# FoneAstra.net
KiCad netlist of a schematic drawn in EAGLE
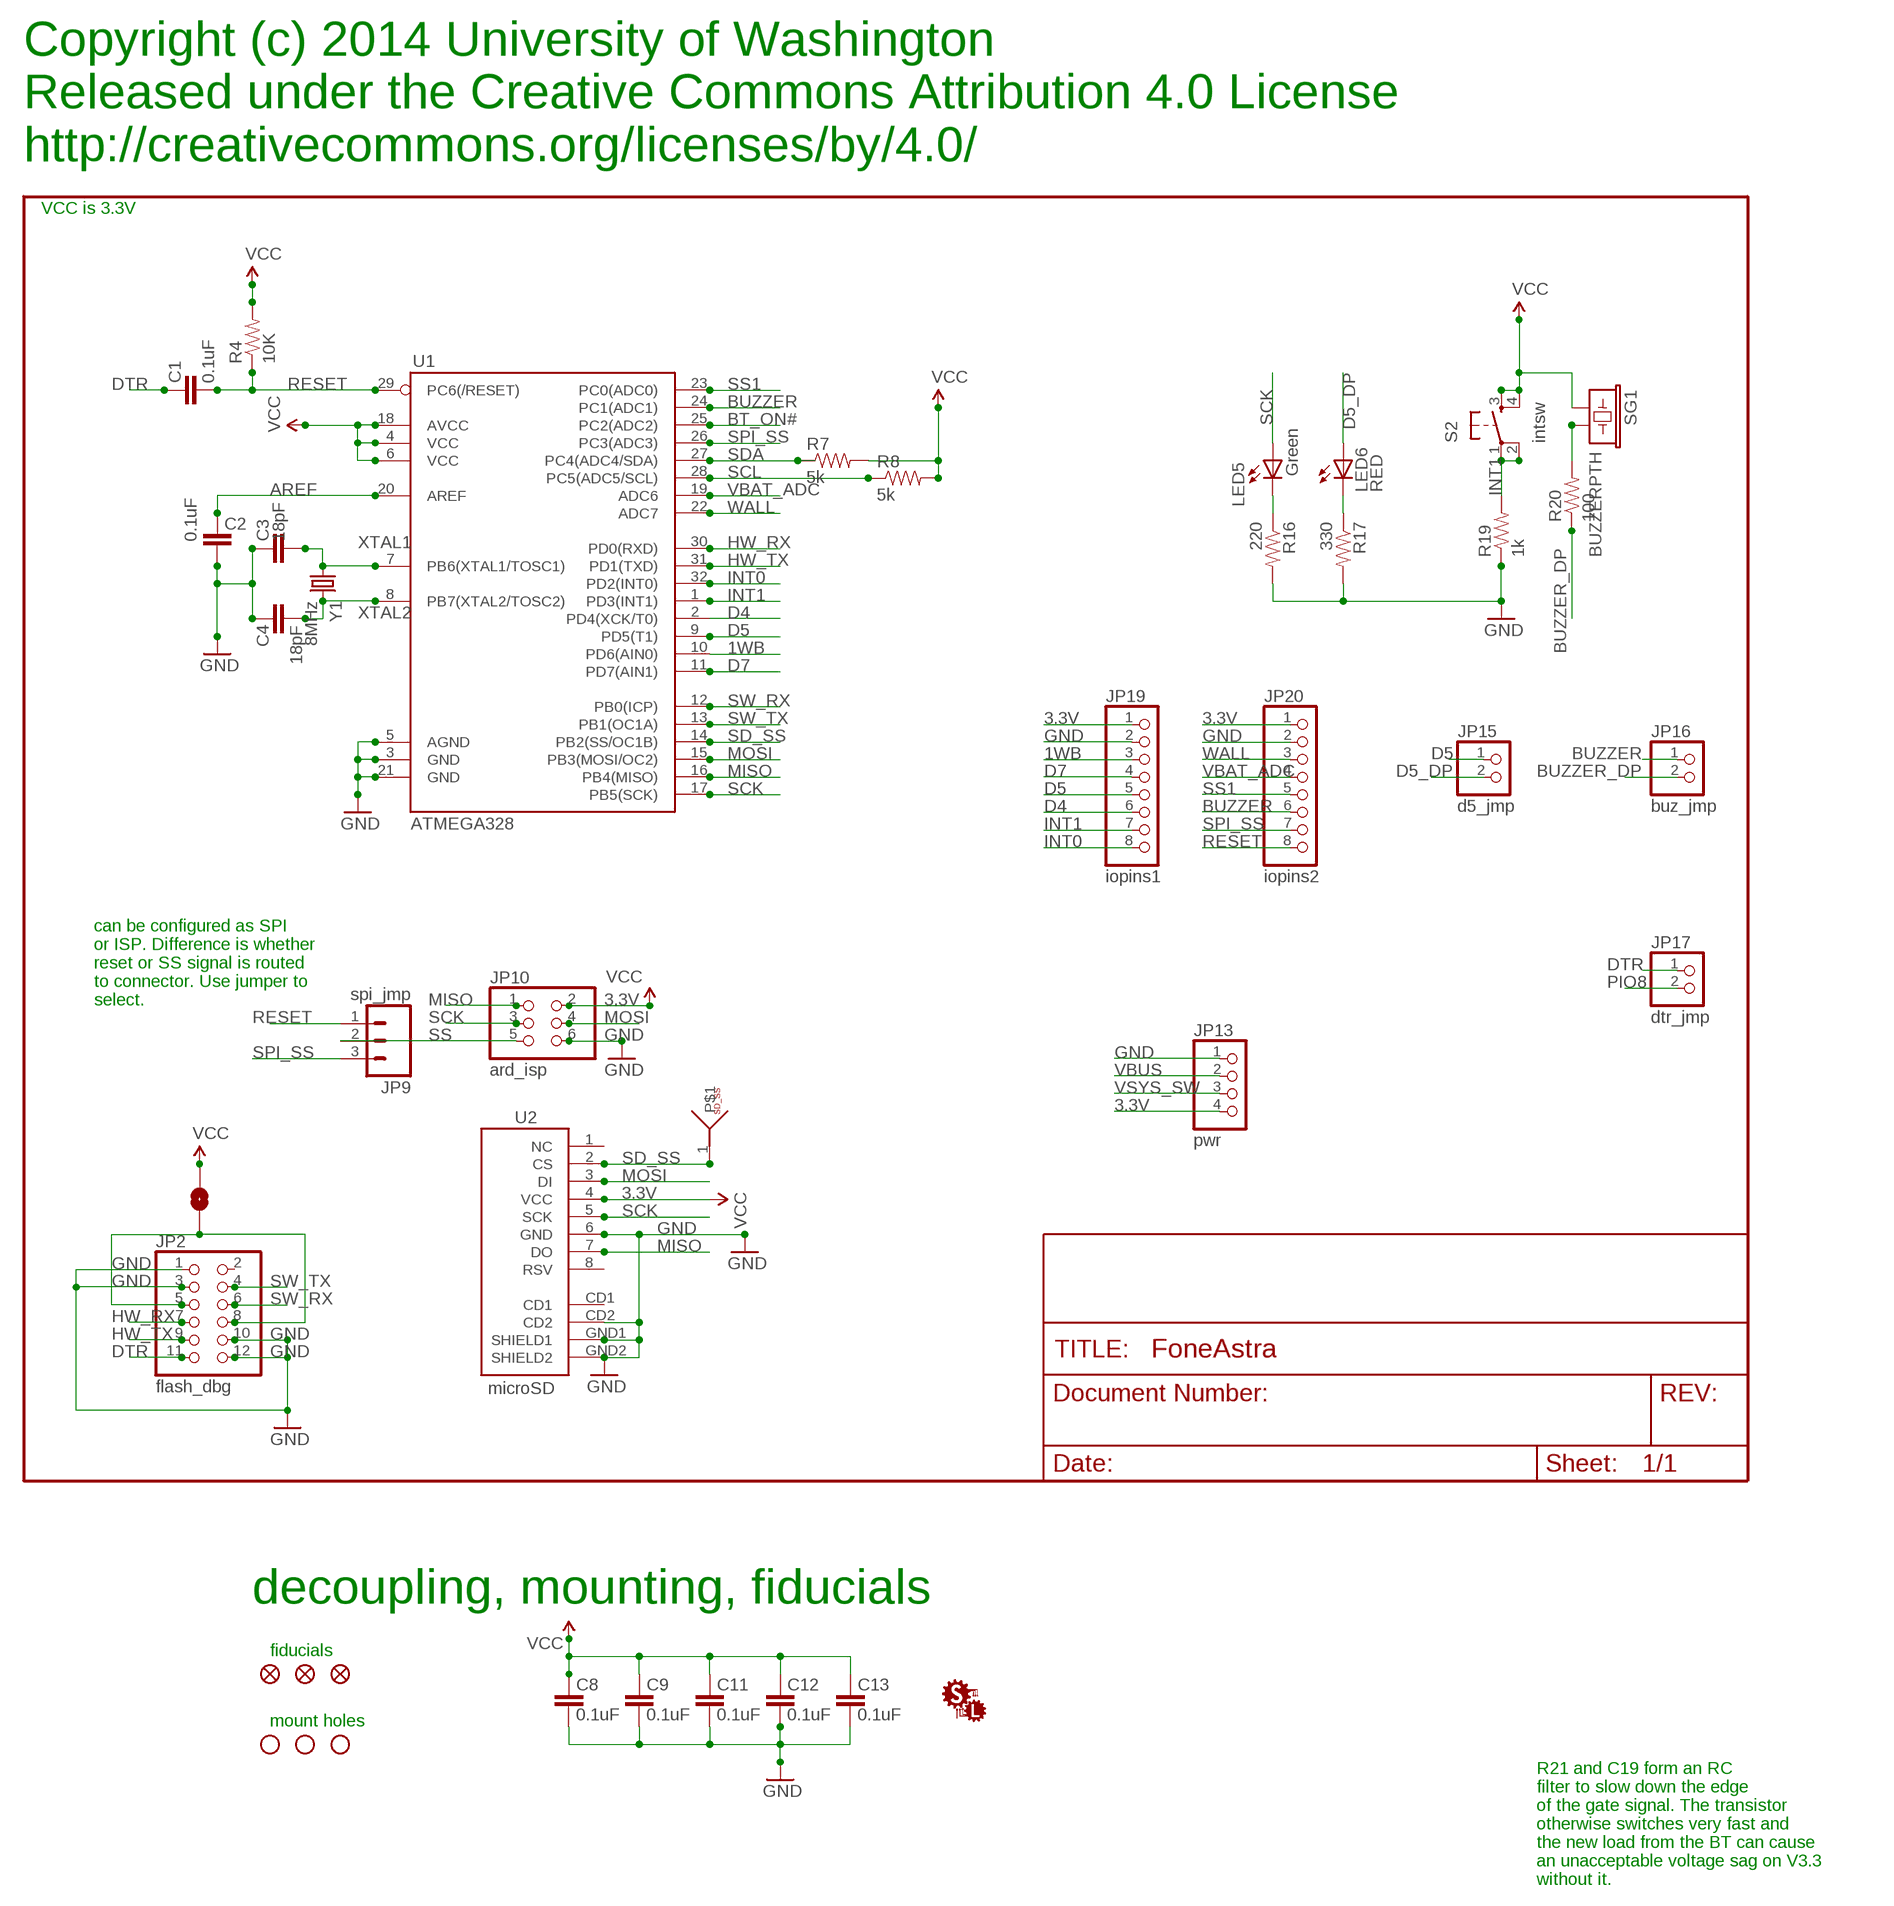
[diagram p0: schematic, sheet 1, part 1 of 2]
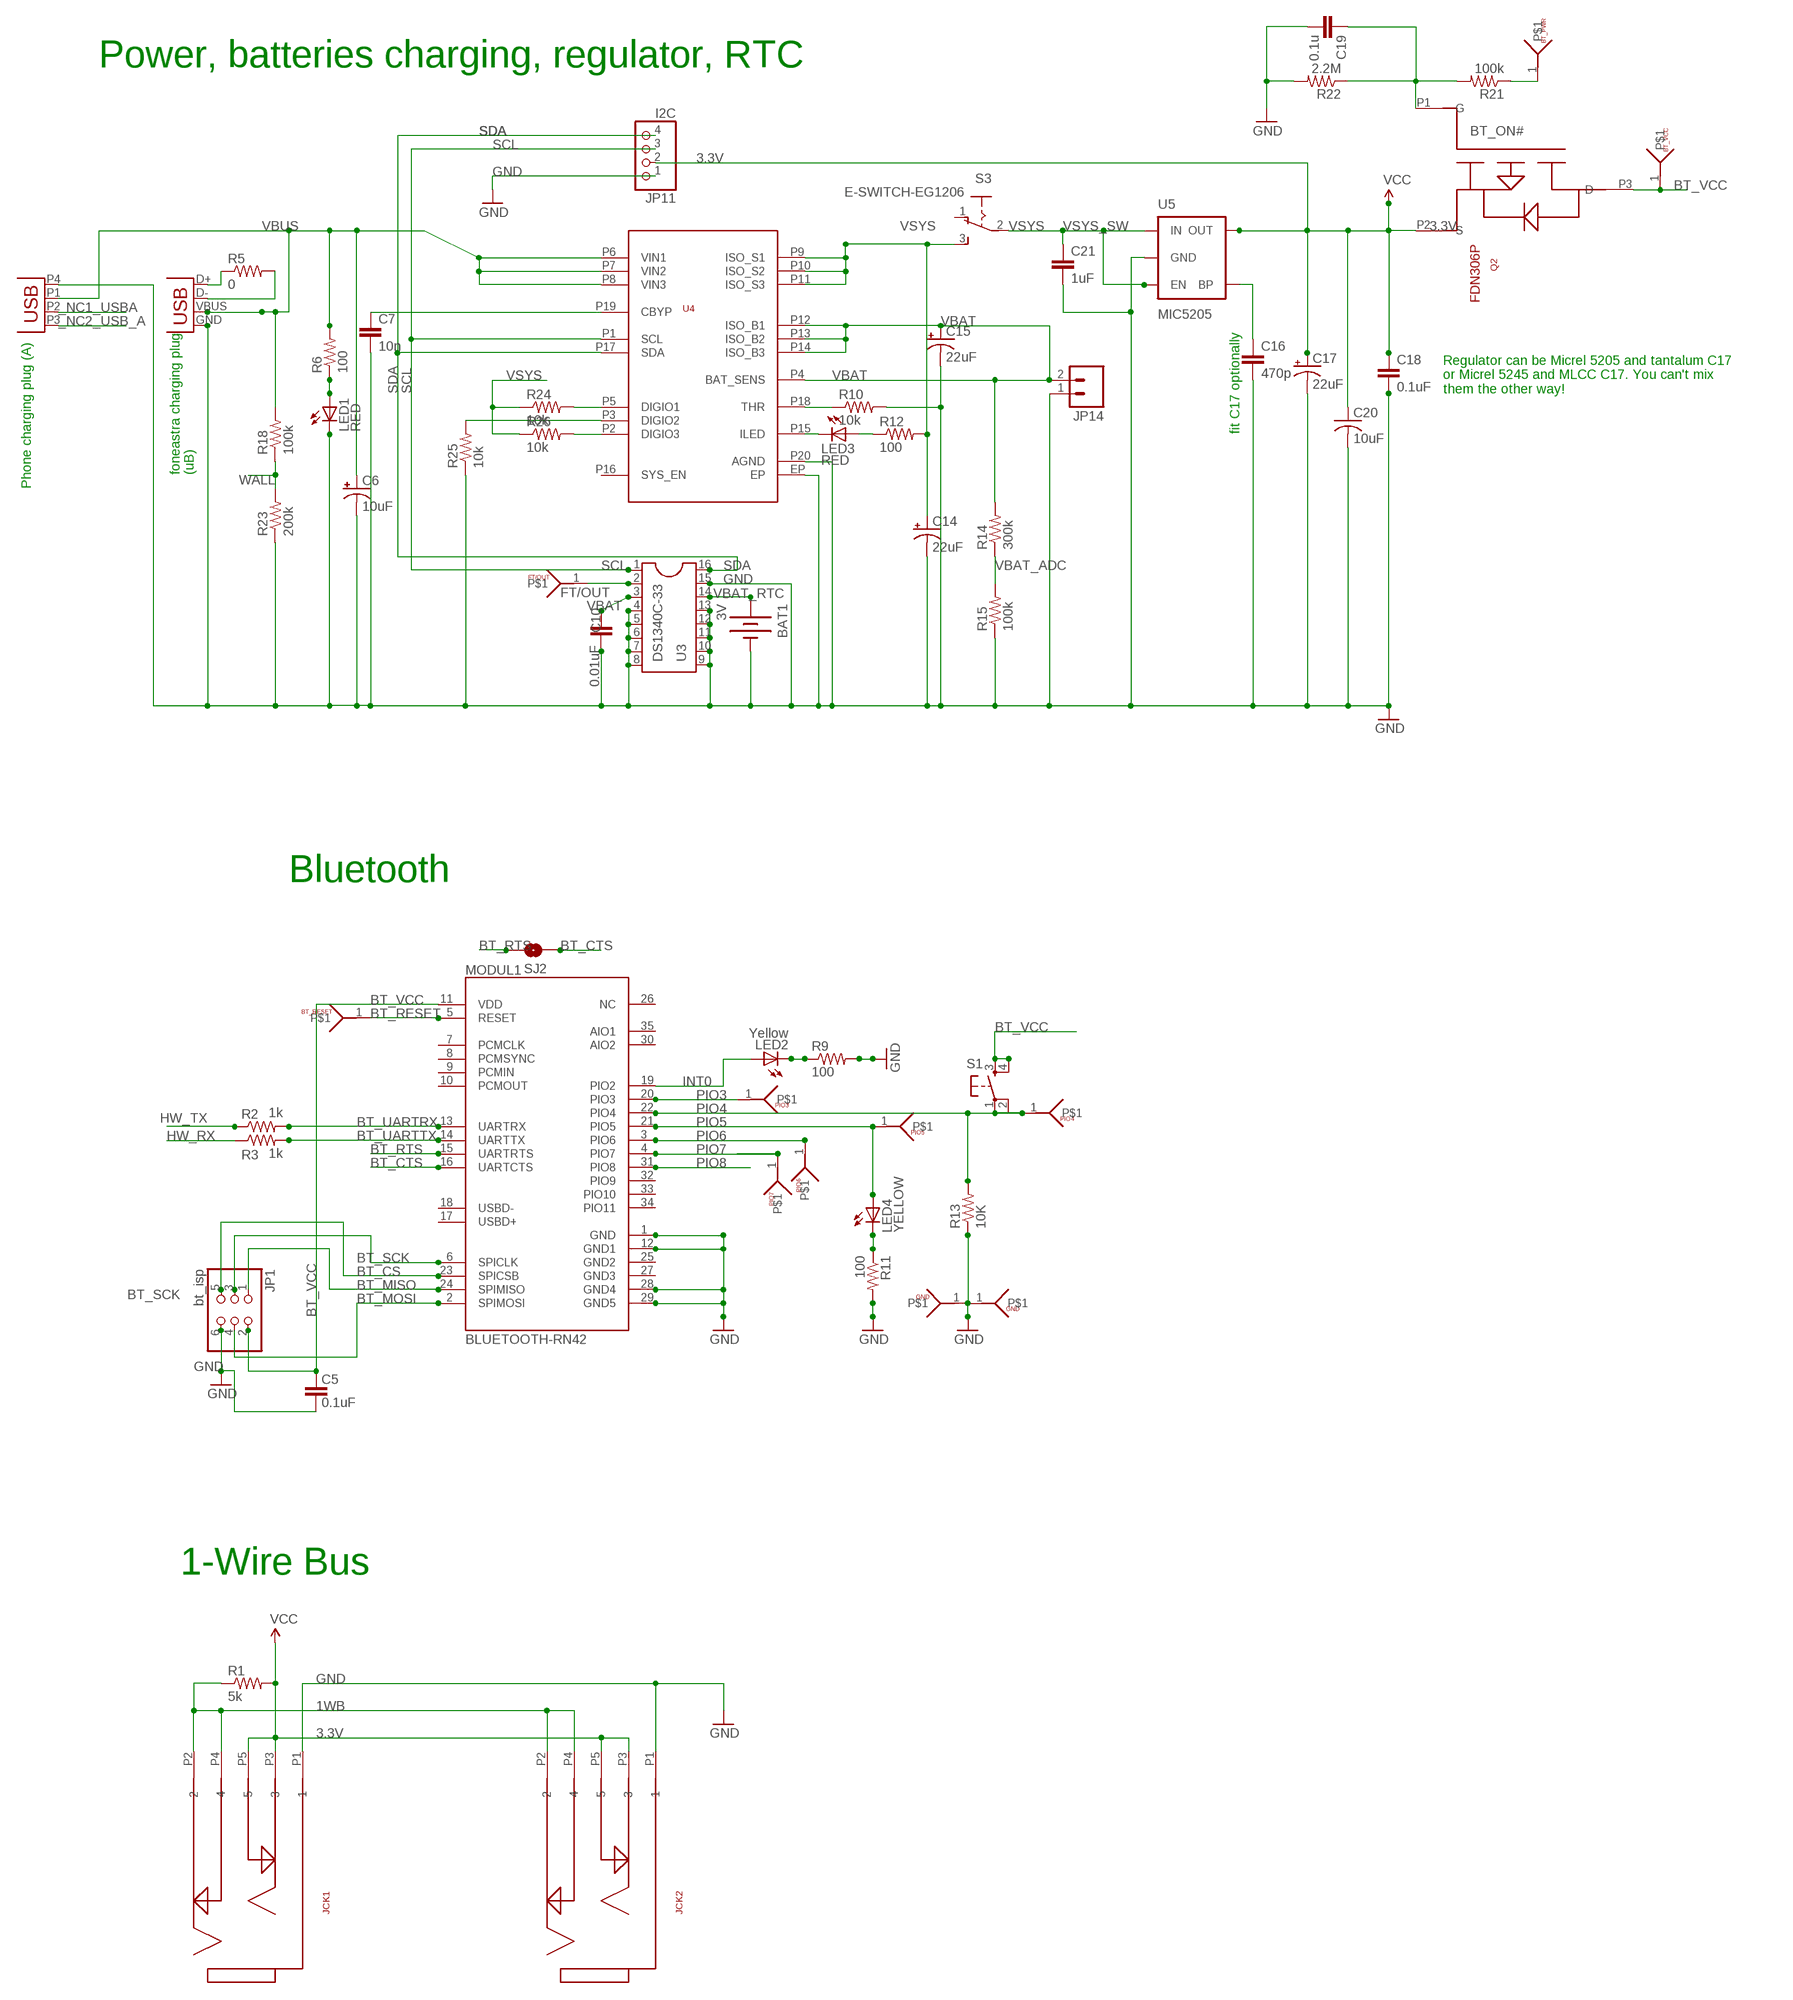
[diagram p1: schematic, sheet 1, part 2 of 2]

(export (version "E")
  (design (tool "Eeschema 10.0.6"))
  (components
    (comp (ref "BAT1")
      (value "3V")
      (footprint "eagle-import:BATTCON_12MM_CURVED")
      (libsource (lib "eagle-import") (part "BATTERY"))
    )
    (comp (ref "C1")
      (value "0.1uF")
      (footprint "eagle-import:0402-CAP")
      (libsource (lib "eagle-import") (part "CAP0402-CAP"))
    )
    (comp (ref "C2")
      (value "0.1uF")
      (footprint "eagle-import:0402-CAP")
      (libsource (lib "eagle-import") (part "CAP0402-CAP"))
    )
    (comp (ref "C3")
      (value "18pF")
      (footprint "eagle-import:0402-CAP")
      (libsource (lib "eagle-import") (part "CAP0402-CAP"))
    )
    (comp (ref "C4")
      (value "18pF")
      (footprint "eagle-import:0402-CAP")
      (libsource (lib "eagle-import") (part "CAP0402-CAP"))
    )
    (comp (ref "C5")
      (value "0.1uF")
      (footprint "eagle-import:0402-CAP")
      (libsource (lib "eagle-import") (part "CAP0402-CAP"))
    )
    (comp (ref "C6")
      (value "10uF")
      (footprint "eagle-import:EIA3216")
      (libsource (lib "eagle-import") (part "CAP_POL1206"))
    )
    (comp (ref "C7")
      (value "10n")
      (footprint "eagle-import:0402-CAP")
      (libsource (lib "eagle-import") (part "CAP0402-CAP"))
    )
    (comp (ref "C8")
      (value "0.1uF")
      (footprint "eagle-import:0402-CAP")
      (libsource (lib "eagle-import") (part "CAP0402-CAP"))
    )
    (comp (ref "C9")
      (value "0.1uF")
      (footprint "eagle-import:0402-CAP")
      (libsource (lib "eagle-import") (part "CAP0402-CAP"))
    )
    (comp (ref "C10")
      (value "0.01uF")
      (footprint "eagle-import:0402-CAP")
      (libsource (lib "eagle-import") (part "CAP0402-CAP"))
    )
    (comp (ref "C11")
      (value "0.1uF")
      (footprint "eagle-import:0402-CAP")
      (libsource (lib "eagle-import") (part "CAP0402-CAP"))
    )
    (comp (ref "C12")
      (value "0.1uF")
      (footprint "eagle-import:0402-CAP")
      (libsource (lib "eagle-import") (part "CAP0402-CAP"))
    )
    (comp (ref "C13")
      (value "0.1uF")
      (footprint "eagle-import:0402-CAP")
      (libsource (lib "eagle-import") (part "CAP0402-CAP"))
    )
    (comp (ref "C14")
      (value "22uF")
      (footprint "eagle-import:EIA3216")
      (libsource (lib "eagle-import") (part "CAP_POL1206"))
    )
    (comp (ref "C15")
      (value "22uF")
      (footprint "eagle-import:EIA3216")
      (libsource (lib "eagle-import") (part "CAP_POL1206"))
    )
    (comp (ref "C16")
      (value "470p")
      (footprint "eagle-import:0402-CAP")
      (libsource (lib "eagle-import") (part "CAP0402-CAP"))
    )
    (comp (ref "C17")
      (value "22uF")
      (footprint "eagle-import:EIA3216")
      (libsource (lib "eagle-import") (part "CAP_POL1206"))
    )
    (comp (ref "C18")
      (value "0.1uF")
      (footprint "eagle-import:0402-CAP")
      (libsource (lib "eagle-import") (part "CAP0402-CAP"))
    )
    (comp (ref "C19")
      (value "0.1u")
      (footprint "eagle-import:0402-CAP")
      (libsource (lib "eagle-import") (part "CAP0402-CAP"))
    )
    (comp (ref "C20")
      (value "10uF")
      (footprint "eagle-import:C0805")
      (libsource (lib "eagle-import") (part "C-USC0805"))
    )
    (comp (ref "C21")
      (value "1uF")
      (footprint "eagle-import:0402-CAP")
      (libsource (lib "eagle-import") (part "CAP0402-CAP"))
    )
    (comp (ref "JCK1")
      (value "35RASMT4BHNTRX")
      (footprint "eagle-import:35RASMT4BHNTRX")
      (libsource (lib "eagle-import") (part "35RASMT4BHNTRX"))
    )
    (comp (ref "JCK2")
      (value "35RASMT4BHNTRX")
      (footprint "eagle-import:35RASMT4BHNTRX")
      (libsource (lib "eagle-import") (part "35RASMT4BHNTRX"))
    )
    (comp (ref "JP1")
      (value "bt_isp")
      (footprint "eagle-import:2X03")
      (libsource (lib "eagle-import") (part "PINHD-2X3"))
    )
    (comp (ref "JP2")
      (value "flash_dbg")
      (footprint "eagle-import:2X06")
      (libsource (lib "eagle-import") (part "PINHD-2X6"))
    )
    (comp (ref "JP3")
      (value "SPARKFUN_FIDUCIAL1.5X3")
      (footprint "eagle-import:SPARKFUN_FIDUCIAL-1.5X3")
      (libsource (lib "eagle-import") (part "SPARKFUN_FIDUCIAL1.5X3"))
    )
    (comp (ref "JP4")
      (value "STAND-OFFTIGHT")
      (footprint "eagle-import:STAND-OFF-TIGHT")
      (libsource (lib "eagle-import") (part "STAND-OFFTIGHT"))
    )
    (comp (ref "JP5")
      (value "SPARKFUN_FIDUCIAL1.5X3")
      (footprint "eagle-import:SPARKFUN_FIDUCIAL-1.5X3")
      (libsource (lib "eagle-import") (part "SPARKFUN_FIDUCIAL1.5X3"))
    )
    (comp (ref "JP6")
      (value "STAND-OFFTIGHT")
      (footprint "eagle-import:STAND-OFF-TIGHT")
      (libsource (lib "eagle-import") (part "STAND-OFFTIGHT"))
    )
    (comp (ref "JP7")
      (value "SPARKFUN_FIDUCIAL1.5X3")
      (footprint "eagle-import:SPARKFUN_FIDUCIAL-1.5X3")
      (libsource (lib "eagle-import") (part "SPARKFUN_FIDUCIAL1.5X3"))
    )
    (comp (ref "JP8")
      (value "STAND-OFFTIGHT")
      (footprint "eagle-import:STAND-OFF-TIGHT")
      (libsource (lib "eagle-import") (part "STAND-OFFTIGHT"))
    )
    (comp (ref "JP9")
      (value "spi_jmp")
      (footprint "eagle-import:1X03")
      (libsource (lib "eagle-import") (part "M03PTH"))
    )
    (comp (ref "JP10")
      (value "ard_isp")
      (footprint "eagle-import:2X03")
      (libsource (lib "eagle-import") (part "PINHD-2X3"))
    )
    (comp (ref "JP11")
      (value "I2C")
      (footprint "eagle-import:1X04")
      (libsource (lib "eagle-import") (part "PINHD-1X4"))
    )
    (comp (ref "JP13")
      (value "pwr")
      (footprint "eagle-import:1X04")
      (libsource (lib "eagle-import") (part "PINHD-1X4"))
    )
    (comp (ref "JP14")
      (value "SPARKFUN_M02JST-PTH-2")
      (footprint "eagle-import:SPARKFUN_JST-2-PTH")
      (libsource (lib "eagle-import") (part "SPARKFUN_M02JST-PTH-2"))
    )
    (comp (ref "JP15")
      (value "d5_jmp")
      (footprint "eagle-import:1X02")
      (libsource (lib "eagle-import") (part "PINHD-1X2"))
    )
    (comp (ref "JP16")
      (value "buz_jmp")
      (footprint "eagle-import:1X02")
      (libsource (lib "eagle-import") (part "PINHD-1X2"))
    )
    (comp (ref "JP17")
      (value "dtr_jmp")
      (footprint "eagle-import:1X02")
      (libsource (lib "eagle-import") (part "PINHD-1X2"))
    )
    (comp (ref "JP19")
      (value "iopins1")
      (footprint "eagle-import:1X08")
      (libsource (lib "eagle-import") (part "PINHD-1X8"))
    )
    (comp (ref "JP20")
      (value "iopins2")
      (footprint "eagle-import:1X08")
      (libsource (lib "eagle-import") (part "PINHD-1X8"))
    )
    (comp (ref "LED1")
      (value "RED")
      (footprint "eagle-import:LXH4")
      (libsource (lib "eagle-import") (part "LED"))
    )
    (comp (ref "LED2")
      (value "Yellow")
      (footprint "eagle-import:LXH4")
      (libsource (lib "eagle-import") (part "LED"))
    )
    (comp (ref "LED3")
      (value "RED")
      (footprint "eagle-import:LXH4")
      (libsource (lib "eagle-import") (part "LED"))
    )
    (comp (ref "LED4")
      (value "YELLOW")
      (footprint "eagle-import:LED-0603")
      (libsource (lib "eagle-import") (part "LED0603"))
    )
    (comp (ref "LED5")
      (value "Green")
      (footprint "eagle-import:LED-0603")
      (libsource (lib "eagle-import") (part "LED0603"))
    )
    (comp (ref "LED6")
      (value "RED")
      (footprint "eagle-import:LXH4")
      (libsource (lib "eagle-import") (part "LED"))
    )
    (comp (ref "MODUL1")
      (value "BLUETOOTH-RN42")
      (footprint "eagle-import:SPARKFUN_RN41")
      (libsource (lib "eagle-import") (part "SPARKFUN_BLUETOOTH-RN41{dblquote}"))
    )
    (comp (ref "Q2")
      (value "FDN306P")
      (footprint "eagle-import:MYSOT23")
      (libsource (lib "eagle-import") (part "FDN306P"))
    )
    (comp (ref "R1")
      (value "5k")
      (footprint "eagle-import:0402-RES")
      (libsource (lib "eagle-import") (part "RESISTOR0402-RES"))
    )
    (comp (ref "R2")
      (value "1k")
      (footprint "eagle-import:0402-RES")
      (libsource (lib "eagle-import") (part "RESISTOR0402-RES"))
    )
    (comp (ref "R3")
      (value "1k")
      (footprint "eagle-import:0402-RES")
      (libsource (lib "eagle-import") (part "RESISTOR0402-RES"))
    )
    (comp (ref "R4")
      (value "10K")
      (footprint "eagle-import:0402-RES")
      (libsource (lib "eagle-import") (part "RESISTOR0402-RES"))
    )
    (comp (ref "R5")
      (value "0")
      (footprint "eagle-import:0402-RES")
      (libsource (lib "eagle-import") (part "RESISTOR0402-RES"))
    )
    (comp (ref "R6")
      (value "100")
      (footprint "eagle-import:0402-RES")
      (libsource (lib "eagle-import") (part "RESISTOR0402-RES"))
    )
    (comp (ref "R7")
      (value "5k")
      (footprint "eagle-import:0402-RES")
      (libsource (lib "eagle-import") (part "RESISTOR0402-RES"))
    )
    (comp (ref "R8")
      (value "5k")
      (footprint "eagle-import:0402-RES")
      (libsource (lib "eagle-import") (part "RESISTOR0402-RES"))
    )
    (comp (ref "R9")
      (value "100")
      (footprint "eagle-import:0402-RES")
      (libsource (lib "eagle-import") (part "RESISTOR0402-RES"))
    )
    (comp (ref "R10")
      (value "10k")
      (footprint "eagle-import:0402-RES")
      (libsource (lib "eagle-import") (part "RESISTOR0402-RES"))
    )
    (comp (ref "R11")
      (value "100")
      (footprint "eagle-import:0402-RES")
      (libsource (lib "eagle-import") (part "RESISTOR0402-RES"))
    )
    (comp (ref "R12")
      (value "100")
      (footprint "eagle-import:0402-RES")
      (libsource (lib "eagle-import") (part "RESISTOR0402-RES"))
    )
    (comp (ref "R13")
      (value "10K")
      (footprint "eagle-import:0402-RES")
      (libsource (lib "eagle-import") (part "RESISTOR0402-RES"))
    )
    (comp (ref "R14")
      (value "300k")
      (footprint "eagle-import:0402-RES")
      (libsource (lib "eagle-import") (part "RESISTOR0402-RES"))
    )
    (comp (ref "R15")
      (value "100k")
      (footprint "eagle-import:0402-RES")
      (libsource (lib "eagle-import") (part "RESISTOR0402-RES"))
    )
    (comp (ref "R16")
      (value "220")
      (footprint "eagle-import:0402-RES")
      (libsource (lib "eagle-import") (part "RESISTOR0402-RES"))
    )
    (comp (ref "R17")
      (value "330")
      (footprint "eagle-import:0402-RES")
      (libsource (lib "eagle-import") (part "RESISTOR0402-RES"))
    )
    (comp (ref "R18")
      (value "100k")
      (footprint "eagle-import:0402-RES")
      (libsource (lib "eagle-import") (part "RESISTOR0402-RES"))
    )
    (comp (ref "R19")
      (value "1k")
      (footprint "eagle-import:0402-RES")
      (libsource (lib "eagle-import") (part "RESISTOR0402-RES"))
    )
    (comp (ref "R20")
      (value "100")
      (footprint "eagle-import:0402-RES")
      (libsource (lib "eagle-import") (part "RESISTOR0402-RES"))
    )
    (comp (ref "R21")
      (value "100k")
      (footprint "eagle-import:0402-RES")
      (libsource (lib "eagle-import") (part "RESISTOR0402-RES"))
    )
    (comp (ref "R22")
      (value "2.2M")
      (footprint "eagle-import:0402-RES")
      (libsource (lib "eagle-import") (part "RESISTOR0402-RES"))
    )
    (comp (ref "R23")
      (value "200k")
      (footprint "eagle-import:0402-RES")
      (libsource (lib "eagle-import") (part "RESISTOR0402-RES"))
    )
    (comp (ref "R24")
      (value "10k")
      (footprint "eagle-import:0402-RES")
      (libsource (lib "eagle-import") (part "RESISTOR0402-RES"))
    )
    (comp (ref "R25")
      (value "10k")
      (footprint "eagle-import:0402-RES")
      (libsource (lib "eagle-import") (part "RESISTOR0402-RES"))
    )
    (comp (ref "R26")
      (value "10k")
      (footprint "eagle-import:0402-RES")
      (libsource (lib "eagle-import") (part "RESISTOR0402-RES"))
    )
    (comp (ref "S1")
      (value "Reset")
      (footprint "eagle-import:TACTILE_SWITCH_SMD")
      (libsource (lib "eagle-import") (part "TAC_SWITCHSMD"))
    )
    (comp (ref "S2")
      (value "intsw")
      (footprint "eagle-import:SPARKFUN_TACTILE_SWITCH_SMD")
      (libsource (lib "eagle-import") (part "SPARKFUN_TAC_SWITCHSMD"))
    )
    (comp (ref "S3")
      (value "E-SWITCH-EG1206")
      (footprint "eagle-import:EG1206")
      (libsource (lib "eagle-import") (part "E-SWITCH-EG1206"))
    )
    (comp (ref "SG1")
      (value "BUZZERPTH")
      (footprint "eagle-import:BUZZER-12MM")
      (libsource (lib "eagle-import") (part "BUZZERPTH"))
    )
    (comp (ref "SJ1")
      (value "SOLDERJUMPERNC2")
      (footprint "eagle-import:SJ_2S-NOTRACE")
      (libsource (lib "eagle-import") (part "SOLDERJUMPERNC2"))
    )
    (comp (ref "SJ2")
      (value "SOLDERJUMPERNC2")
      (footprint "eagle-import:SJ_2S-NOTRACE")
      (libsource (lib "eagle-import") (part "SOLDERJUMPERNC2"))
    )
    (comp (ref "TP1")
      (value "BT_RESET")
      (footprint "eagle-import:TESTPOINT")
      (libsource (lib "eagle-import") (part "TESTPOINT"))
    )
    (comp (ref "TP2")
      (value "FT/OUT")
      (footprint "eagle-import:TESTPOINT")
      (libsource (lib "eagle-import") (part "TESTPOINT"))
    )
    (comp (ref "TP3")
      (value "SD_SS")
      (footprint "eagle-import:TESTPOINT")
      (libsource (lib "eagle-import") (part "TESTPOINT"))
    )
    (comp (ref "TP4")
      (value "PIO3")
      (footprint "eagle-import:TESTPOINT")
      (libsource (lib "eagle-import") (part "TESTPOINT"))
    )
    (comp (ref "TP5")
      (value "PIO7")
      (footprint "eagle-import:TESTPOINT")
      (libsource (lib "eagle-import") (part "TESTPOINT"))
    )
    (comp (ref "TP6")
      (value "PIO6")
      (footprint "eagle-import:TESTPOINT")
      (libsource (lib "eagle-import") (part "TESTPOINT"))
    )
    (comp (ref "TP7")
      (value "PIO5")
      (footprint "eagle-import:TESTPOINT")
      (libsource (lib "eagle-import") (part "TESTPOINT"))
    )
    (comp (ref "TP8")
      (value "GND")
      (footprint "eagle-import:TESTPOINT")
      (libsource (lib "eagle-import") (part "TESTPOINT"))
    )
    (comp (ref "TP9")
      (value "GND")
      (footprint "eagle-import:TESTPOINT")
      (libsource (lib "eagle-import") (part "TESTPOINT"))
    )
    (comp (ref "TP10")
      (value "PIO4")
      (footprint "eagle-import:TESTPOINT")
      (libsource (lib "eagle-import") (part "TESTPOINT"))
    )
    (comp (ref "TP11")
      (value "BT_PWR")
      (footprint "eagle-import:TESTPOINT")
      (libsource (lib "eagle-import") (part "TESTPOINT"))
    )
    (comp (ref "TP12")
      (value "BT_VCC")
      (footprint "eagle-import:TESTPOINT")
      (libsource (lib "eagle-import") (part "TESTPOINT"))
    )
    (comp (ref "U$2")
      (value "SHIFT_LOGO")
      (footprint "eagle-import:SHIFT_LOGO")
      (libsource (lib "eagle-import") (part "SHIFT_LOGO"))
    )
    (comp (ref "U1")
      (value "ATMEGA328")
      (footprint "eagle-import:TQFP32-08")
      (libsource (lib "eagle-import") (part "ATMEGA168"))
    )
    (comp (ref "U2")
      (value "microSD")
      (footprint "eagle-import:SPARKFUN_MICRO-SD-SOCKET-PP")
      (libsource (lib "eagle-import") (part "SPARKFUN_USD-SOCKETSMD"))
    )
    (comp (ref "U3")
      (value "DS1340C-33")
      (footprint "eagle-import:SO16L")
      (libsource (lib "eagle-import") (part "DS1340C-33"))
    )
    (comp (ref "U4")
      (value "ADP5062")
      (footprint "eagle-import:LFCSP_WQ20")
      (libsource (lib "eagle-import") (part "ADP5062"))
    )
    (comp (ref "U5")
      (value "MIC5205")
      (footprint "eagle-import:SOT23-5")
      (libsource (lib "eagle-import") (part "V_REG_LDOSMD"))
    )
    (comp (ref "X1")
      (value "MOLEX48204_USB_A_VERT")
      (footprint "eagle-import:MOLEX48204_USB_A_VERT")
      (libsource (lib "eagle-import") (part "MOLEX48204_USB_A_VERT"))
    )
    (comp (ref "X2")
      (value "Micro USB")
      (footprint "eagle-import:USB-MICROB")
      (libsource (lib "eagle-import") (part "USB-MICROB"))
    )
    (comp (ref "Y1")
      (value "8MHz")
      (footprint "eagle-import:HC49_S")
      (libsource (lib "eagle-import") (part "CRYSTALHC49S"))
    )
  )
  (nets
    (net (code "1") (name "/1WB") (class "Default")
      (node (ref "JCK1") (pin "P2") (pinfunction "2_P2") (pintype "bidirectional"))
      (node (ref "JCK1") (pin "P4") (pinfunction "4_P4") (pintype "bidirectional"))
      (node (ref "JCK2") (pin "P2") (pinfunction "2_P2") (pintype "bidirectional"))
      (node (ref "JCK2") (pin "P4") (pinfunction "4_P4") (pintype "bidirectional"))
      (node (ref "JP19") (pin "3") (pinfunction "3_3") (pintype "passive"))
      (node (ref "R1") (pin "1") (pinfunction "1_1") (pintype "passive"))
      (node (ref "U1") (pin "10") (pinfunction "PD6(AIN0)_10") (pintype "bidirectional"))
    )
    (net (code "2") (name "/AREF") (class "Default")
      (node (ref "C2") (pin "2") (pinfunction "2_2") (pintype "passive"))
      (node (ref "U1") (pin "20") (pinfunction "AREF_20") (pintype "bidirectional"))
    )
    (net (code "3") (name "/BT_CS") (class "Default")
      (node (ref "JP1") (pin "5") (pinfunction "5_5") (pintype "passive"))
      (node (ref "MODUL1") (pin "23") (pinfunction "SPICSB_23") (pintype "bidirectional"))
    )
    (net (code "4") (name "/BT_CTS") (class "Default")
      (node (ref "MODUL1") (pin "16") (pinfunction "UARTCTS_16") (pintype "bidirectional"))
      (node (ref "SJ2") (pin "1") (pinfunction "1_1") (pintype "passive"))
    )
    (net (code "5") (name "/BT_MISO") (class "Default")
      (node (ref "JP1") (pin "1") (pinfunction "1_1") (pintype "passive"))
      (node (ref "MODUL1") (pin "24") (pinfunction "SPIMISO_24") (pintype "bidirectional"))
    )
    (net (code "6") (name "/BT_MOSI") (class "Default")
      (node (ref "JP1") (pin "4") (pinfunction "4_4") (pintype "passive"))
      (node (ref "MODUL1") (pin "2") (pinfunction "SPIMOSI_2") (pintype "bidirectional"))
    )
    (net (code "7") (name "/BT_ON#") (class "Default")
      (node (ref "R21") (pin "1") (pinfunction "1_1") (pintype "passive"))
      (node (ref "TP11") (pin "1") (pinfunction "P$1_1") (pintype "bidirectional"))
      (node (ref "U1") (pin "25") (pinfunction "PC2(ADC2)_25") (pintype "bidirectional"))
    )
    (net (code "8") (name "/BT_RESET") (class "Default")
      (node (ref "MODUL1") (pin "5") (pinfunction "RESET_5") (pintype "bidirectional"))
      (node (ref "TP1") (pin "1") (pinfunction "P$1_1") (pintype "bidirectional"))
    )
    (net (code "9") (name "/BT_RTS") (class "Default")
      (node (ref "MODUL1") (pin "15") (pinfunction "UARTRTS_15") (pintype "bidirectional"))
      (node (ref "SJ2") (pin "2") (pinfunction "2_2") (pintype "passive"))
    )
    (net (code "10") (name "/BT_SCK") (class "Default")
      (node (ref "JP1") (pin "3") (pinfunction "3_3") (pintype "passive"))
      (node (ref "MODUL1") (pin "6") (pinfunction "SPICLK_6") (pintype "bidirectional"))
    )
    (net (code "11") (name "/BT_UARTRX") (class "Default")
      (node (ref "MODUL1") (pin "13") (pinfunction "UARTRX_13") (pintype "bidirectional"))
      (node (ref "R2") (pin "2") (pinfunction "2_2") (pintype "passive"))
    )
    (net (code "12") (name "/BT_UARTTX") (class "Default")
      (node (ref "MODUL1") (pin "14") (pinfunction "UARTTX_14") (pintype "bidirectional"))
      (node (ref "R3") (pin "2") (pinfunction "2_2") (pintype "passive"))
    )
    (net (code "13") (name "/BT_VCC") (class "Default")
      (node (ref "C5") (pin "2") (pinfunction "2_2") (pintype "passive"))
      (node (ref "JP1") (pin "2") (pinfunction "2_2") (pintype "passive"))
      (node (ref "MODUL1") (pin "11") (pinfunction "VDD_11") (pintype "bidirectional"))
      (node (ref "Q2") (pin "P3") (pinfunction "D_P3") (pintype "bidirectional"))
      (node (ref "S1") (pin "3") (pinfunction "3_3") (pintype "passive"))
      (node (ref "S1") (pin "4") (pinfunction "4_4") (pintype "passive"))
      (node (ref "TP12") (pin "1") (pinfunction "P$1_1") (pintype "bidirectional"))
    )
    (net (code "14") (name "/BUZZER") (class "Default")
      (node (ref "JP16") (pin "1") (pinfunction "1_1") (pintype "passive"))
      (node (ref "JP20") (pin "6") (pinfunction "6_6") (pintype "passive"))
      (node (ref "U1") (pin "24") (pinfunction "PC1(ADC1)_24") (pintype "bidirectional"))
    )
    (net (code "15") (name "/BUZZER_DP") (class "Default")
      (node (ref "JP16") (pin "2") (pinfunction "2_2") (pintype "passive"))
      (node (ref "R20") (pin "1") (pinfunction "1_1") (pintype "passive"))
    )
    (net (code "16") (name "/D4") (class "Default")
      (node (ref "JP19") (pin "6") (pinfunction "6_6") (pintype "passive"))
      (node (ref "U1") (pin "2") (pinfunction "PD4(XCK/T0)_2") (pintype "bidirectional"))
    )
    (net (code "17") (name "/D5") (class "Default")
      (node (ref "JP15") (pin "1") (pinfunction "1_1") (pintype "passive"))
      (node (ref "JP19") (pin "5") (pinfunction "5_5") (pintype "passive"))
      (node (ref "U1") (pin "9") (pinfunction "PD5(T1)_9") (pintype "bidirectional"))
    )
    (net (code "18") (name "/D5_DP") (class "Default")
      (node (ref "JP15") (pin "2") (pinfunction "2_2") (pintype "passive"))
      (node (ref "LED6") (pin "A") (pinfunction "A_A") (pintype "passive"))
    )
    (net (code "19") (name "/D7") (class "Default")
      (node (ref "JP19") (pin "4") (pinfunction "4_4") (pintype "passive"))
      (node (ref "U1") (pin "11") (pinfunction "PD7(AIN1)_11") (pintype "bidirectional"))
    )
    (net (code "20") (name "/DTR") (class "Default")
      (node (ref "C1") (pin "2") (pinfunction "2_2") (pintype "passive"))
      (node (ref "JP17") (pin "1") (pinfunction "1_1") (pintype "passive"))
      (node (ref "JP2") (pin "11") (pinfunction "11_11") (pintype "passive"))
    )
    (net (code "21") (name "/FT{slash}OUT") (class "Default")
      (node (ref "TP2") (pin "1") (pinfunction "P$1_1") (pintype "bidirectional"))
      (node (ref "U3") (pin "2") (pinfunction "2_2") (pintype "passive"))
    )
    (net (code "22") (name "/HW_RX") (class "Default")
      (node (ref "JP2") (pin "7") (pinfunction "7_7") (pintype "passive"))
      (node (ref "R3") (pin "1") (pinfunction "1_1") (pintype "passive"))
      (node (ref "U1") (pin "30") (pinfunction "PD0(RXD)_30") (pintype "bidirectional"))
    )
    (net (code "23") (name "/HW_TX") (class "Default")
      (node (ref "JP2") (pin "9") (pinfunction "9_9") (pintype "passive"))
      (node (ref "R2") (pin "1") (pinfunction "1_1") (pintype "passive"))
      (node (ref "U1") (pin "31") (pinfunction "PD1(TXD)_31") (pintype "bidirectional"))
    )
    (net (code "24") (name "/INT0") (class "Default")
      (node (ref "JP19") (pin "8") (pinfunction "8_8") (pintype "passive"))
      (node (ref "LED2") (pin "A") (pinfunction "A_A") (pintype "passive"))
      (node (ref "MODUL1") (pin "19") (pinfunction "PIO2_19") (pintype "bidirectional"))
      (node (ref "U1") (pin "32") (pinfunction "PD2(INT0)_32") (pintype "bidirectional"))
    )
    (net (code "25") (name "/INT1") (class "Default")
      (node (ref "JP19") (pin "7") (pinfunction "7_7") (pintype "passive"))
      (node (ref "R19") (pin "2") (pinfunction "2_2") (pintype "passive"))
      (node (ref "S2") (pin "1") (pinfunction "1_1") (pintype "passive"))
      (node (ref "S2") (pin "2") (pinfunction "2_2") (pintype "passive"))
      (node (ref "U1") (pin "1") (pinfunction "PD3(INT1)_1") (pintype "bidirectional"))
    )
    (net (code "26") (name "/MISO") (class "Default")
      (node (ref "JP10") (pin "1") (pinfunction "1_1") (pintype "passive"))
      (node (ref "U1") (pin "16") (pinfunction "PB4(MISO)_16") (pintype "bidirectional"))
      (node (ref "U2") (pin "7") (pinfunction "DO_7") (pintype "bidirectional"))
    )
    (net (code "27") (name "/MOSI") (class "Default")
      (node (ref "JP10") (pin "4") (pinfunction "4_4") (pintype "passive"))
      (node (ref "U1") (pin "15") (pinfunction "PB3(MOSI/OC2)_15") (pintype "bidirectional"))
      (node (ref "U2") (pin "3") (pinfunction "DI_3") (pintype "bidirectional"))
    )
    (net (code "28") (name "/PIO3") (class "Default")
      (node (ref "MODUL1") (pin "20") (pinfunction "PIO3_20") (pintype "bidirectional"))
      (node (ref "TP4") (pin "1") (pinfunction "P$1_1") (pintype "bidirectional"))
    )
    (net (code "29") (name "/PIO4") (class "Default")
      (node (ref "MODUL1") (pin "22") (pinfunction "PIO4_22") (pintype "bidirectional"))
      (node (ref "R13") (pin "2") (pinfunction "2_2") (pintype "passive"))
      (node (ref "S1") (pin "1") (pinfunction "1_1") (pintype "passive"))
      (node (ref "S1") (pin "2") (pinfunction "2_2") (pintype "passive"))
      (node (ref "TP10") (pin "1") (pinfunction "P$1_1") (pintype "bidirectional"))
    )
    (net (code "30") (name "/PIO5") (class "Default")
      (node (ref "LED4") (pin "A") (pinfunction "A_A") (pintype "passive"))
      (node (ref "MODUL1") (pin "21") (pinfunction "PIO5_21") (pintype "bidirectional"))
      (node (ref "TP7") (pin "1") (pinfunction "P$1_1") (pintype "bidirectional"))
    )
    (net (code "31") (name "/PIO6") (class "Default")
      (node (ref "MODUL1") (pin "3") (pinfunction "PIO6_3") (pintype "bidirectional"))
      (node (ref "TP6") (pin "1") (pinfunction "P$1_1") (pintype "bidirectional"))
    )
    (net (code "32") (name "/PIO7") (class "Default")
      (node (ref "MODUL1") (pin "4") (pinfunction "PIO7_4") (pintype "bidirectional"))
      (node (ref "TP5") (pin "1") (pinfunction "P$1_1") (pintype "bidirectional"))
    )
    (net (code "33") (name "/PIO8") (class "Default")
      (node (ref "JP17") (pin "2") (pinfunction "2_2") (pintype "passive"))
      (node (ref "MODUL1") (pin "31") (pinfunction "PIO8_31") (pintype "bidirectional"))
    )
    (net (code "34") (name "/RESET") (class "Default")
      (node (ref "C1") (pin "1") (pinfunction "1_1") (pintype "passive"))
      (node (ref "JP20") (pin "8") (pinfunction "8_8") (pintype "passive"))
      (node (ref "JP9") (pin "1") (pinfunction "1_1") (pintype "passive"))
      (node (ref "R4") (pin "1") (pinfunction "1_1") (pintype "passive"))
      (node (ref "U1") (pin "29") (pinfunction "PC6(/RESET)_29") (pintype "bidirectional"))
    )
    (net (code "35") (name "/SCK") (class "Default")
      (node (ref "JP10") (pin "3") (pinfunction "3_3") (pintype "passive"))
      (node (ref "LED5") (pin "A") (pinfunction "A_A") (pintype "passive"))
      (node (ref "U1") (pin "17") (pinfunction "PB5(SCK)_17") (pintype "bidirectional"))
      (node (ref "U2") (pin "5") (pinfunction "SCK_5") (pintype "bidirectional"))
    )
    (net (code "36") (name "/SCL") (class "Default")
      (node (ref "JP11") (pin "3") (pinfunction "3_3") (pintype "passive"))
      (node (ref "R8") (pin "1") (pinfunction "1_1") (pintype "passive"))
      (node (ref "U1") (pin "28") (pinfunction "PC5(ADC5/SCL)_28") (pintype "bidirectional"))
      (node (ref "U3") (pin "1") (pinfunction "1_1") (pintype "passive"))
      (node (ref "U4") (pin "P1") (pinfunction "SCL_P1") (pintype "bidirectional"))
    )
    (net (code "37") (name "/SDA") (class "Default")
      (node (ref "JP11") (pin "4") (pinfunction "4_4") (pintype "passive"))
      (node (ref "R7") (pin "1") (pinfunction "1_1") (pintype "passive"))
      (node (ref "U1") (pin "27") (pinfunction "PC4(ADC4/SDA)_27") (pintype "bidirectional"))
      (node (ref "U3") (pin "16") (pinfunction "16_16") (pintype "passive"))
      (node (ref "U4") (pin "P17") (pinfunction "SDA_P17") (pintype "bidirectional"))
    )
    (net (code "38") (name "/SD_SS") (class "Default")
      (node (ref "TP3") (pin "1") (pinfunction "P$1_1") (pintype "bidirectional"))
      (node (ref "U1") (pin "14") (pinfunction "PB2(SS/OC1B)_14") (pintype "bidirectional"))
      (node (ref "U2") (pin "2") (pinfunction "CS_2") (pintype "bidirectional"))
    )
    (net (code "39") (name "/SPI_SS") (class "Default")
      (node (ref "JP20") (pin "7") (pinfunction "7_7") (pintype "passive"))
      (node (ref "JP9") (pin "3") (pinfunction "3_3") (pintype "passive"))
      (node (ref "U1") (pin "26") (pinfunction "PC3(ADC3)_26") (pintype "bidirectional"))
    )
    (net (code "40") (name "/SS") (class "Default")
      (node (ref "JP10") (pin "5") (pinfunction "5_5") (pintype "passive"))
      (node (ref "JP9") (pin "2") (pinfunction "2_2") (pintype "passive"))
    )
    (net (code "41") (name "/SS1") (class "Default")
      (node (ref "JP20") (pin "5") (pinfunction "5_5") (pintype "passive"))
      (node (ref "U1") (pin "23") (pinfunction "PC0(ADC0)_23") (pintype "bidirectional"))
    )
    (net (code "42") (name "/SW_RX") (class "Default")
      (node (ref "JP2") (pin "6") (pinfunction "6_6") (pintype "passive"))
      (node (ref "U1") (pin "12") (pinfunction "PB0(ICP)_12") (pintype "bidirectional"))
    )
    (net (code "43") (name "/SW_TX") (class "Default")
      (node (ref "JP2") (pin "4") (pinfunction "4_4") (pintype "passive"))
      (node (ref "U1") (pin "13") (pinfunction "PB1(OC1A)_13") (pintype "bidirectional"))
    )
    (net (code "44") (name "/VBAT") (class "Default")
      (node (ref "C10") (pin "2") (pinfunction "2_2") (pintype "passive"))
      (node (ref "C15") (pin "A") (pinfunction "+_A") (pintype "passive"))
      (node (ref "JP14") (pin "2") (pinfunction "2_2") (pintype "passive"))
      (node (ref "R14") (pin "2") (pinfunction "2_2") (pintype "passive"))
      (node (ref "U3") (pin "3") (pinfunction "3_3") (pintype "passive"))
      (node (ref "U4") (pin "P12") (pinfunction "ISO_B1_P12") (pintype "bidirectional"))
      (node (ref "U4") (pin "P13") (pinfunction "ISO_B2_P13") (pintype "bidirectional"))
      (node (ref "U4") (pin "P14") (pinfunction "ISO_B3_P14") (pintype "bidirectional"))
      (node (ref "U4") (pin "P4") (pinfunction "BAT_SENS_P4") (pintype "bidirectional"))
    )
    (net (code "45") (name "/VBAT_ADC") (class "Default")
      (node (ref "JP20") (pin "4") (pinfunction "4_4") (pintype "passive"))
      (node (ref "R14") (pin "1") (pinfunction "1_1") (pintype "passive"))
      (node (ref "R15") (pin "2") (pinfunction "2_2") (pintype "passive"))
      (node (ref "U1") (pin "19") (pinfunction "ADC6_19") (pintype "bidirectional"))
    )
    (net (code "46") (name "/VBAT_RTC") (class "Default")
      (node (ref "BAT1") (pin "PWR@1") (pinfunction "+_PWR@1") (pintype "power_in"))
      (node (ref "U3") (pin "14") (pinfunction "14_14") (pintype "passive"))
    )
    (net (code "47") (name "/VBUS") (class "Default")
      (node (ref "C6") (pin "A") (pinfunction "+_A") (pintype "passive"))
      (node (ref "JP13") (pin "2") (pinfunction "2_2") (pintype "passive"))
      (node (ref "R18") (pin "2") (pinfunction "2_2") (pintype "passive"))
      (node (ref "R6") (pin "2") (pinfunction "2_2") (pintype "passive"))
      (node (ref "U4") (pin "P6") (pinfunction "VIN1_P6") (pintype "bidirectional"))
      (node (ref "U4") (pin "P7") (pinfunction "VIN2_P7") (pintype "bidirectional"))
      (node (ref "U4") (pin "P8") (pinfunction "VIN3_P8") (pintype "bidirectional"))
      (node (ref "X1") (pin "P1") (pinfunction "VBUS_P1") (pintype "bidirectional"))
      (node (ref "X2") (pin "VBUS") (pinfunction "VBUS_VBUS") (pintype "bidirectional"))
    )
    (net (code "48") (name "/VSYS") (class "Default")
      (node (ref "C14") (pin "A") (pinfunction "+_A") (pintype "passive"))
      (node (ref "R12") (pin "2") (pinfunction "2_2") (pintype "passive"))
      (node (ref "R24") (pin "1") (pinfunction "1_1") (pintype "passive"))
      (node (ref "R26") (pin "1") (pinfunction "1_1") (pintype "passive"))
      (node (ref "S3") (pin "3") (pinfunction "S_3") (pintype "passive"))
      (node (ref "U4") (pin "P10") (pinfunction "ISO_S2_P10") (pintype "bidirectional"))
      (node (ref "U4") (pin "P11") (pinfunction "ISO_S3_P11") (pintype "bidirectional"))
      (node (ref "U4") (pin "P9") (pinfunction "ISO_S1_P9") (pintype "bidirectional"))
    )
    (net (code "49") (name "/VSYS_SW") (class "Default")
      (node (ref "C21") (pin "1") (pinfunction "1_1") (pintype "passive"))
      (node (ref "JP13") (pin "3") (pinfunction "3_3") (pintype "passive"))
      (node (ref "S3") (pin "2") (pinfunction "P_2") (pintype "passive"))
      (node (ref "U5") (pin "1") (pinfunction "IN_1") (pintype "input"))
      (node (ref "U5") (pin "3") (pinfunction "EN_3") (pintype "input"))
    )
    (net (code "50") (name "/WALL") (class "Default")
      (node (ref "JP20") (pin "3") (pinfunction "3_3") (pintype "passive"))
      (node (ref "R18") (pin "1") (pinfunction "1_1") (pintype "passive"))
      (node (ref "R23") (pin "2") (pinfunction "2_2") (pintype "passive"))
      (node (ref "U1") (pin "22") (pinfunction "ADC7_22") (pintype "bidirectional"))
    )
    (net (code "51") (name "/XTAL1") (class "Default")
      (node (ref "C3") (pin "1") (pinfunction "1_1") (pintype "passive"))
      (node (ref "U1") (pin "7") (pinfunction "PB6(XTAL1/TOSC1)_7") (pintype "bidirectional"))
      (node (ref "Y1") (pin "1") (pinfunction "1_1") (pintype "passive"))
    )
    (net (code "52") (name "/XTAL2") (class "Default")
      (node (ref "C4") (pin "1") (pinfunction "1_1") (pintype "passive"))
      (node (ref "U1") (pin "8") (pinfunction "PB7(XTAL2/TOSC2)_8") (pintype "bidirectional"))
      (node (ref "Y1") (pin "2") (pinfunction "2_2") (pintype "passive"))
    )
    (net (code "53") (name "/_NC1_USBA") (class "Default")
      (node (ref "X1") (pin "P2") (pinfunction "D-_P2") (pintype "bidirectional"))
    )
    (net (code "54") (name "/_NC2_USB_A") (class "Default")
      (node (ref "X1") (pin "P3") (pinfunction "D+_P3") (pintype "bidirectional"))
    )
    (net (code "55") (name "GND") (class "Default")
      (node (ref "BAT1") (pin "GND") (pinfunction "-_GND") (pintype "power_in"))
      (node (ref "C10") (pin "1") (pinfunction "1_1") (pintype "passive"))
      (node (ref "C11") (pin "1") (pinfunction "1_1") (pintype "passive"))
      (node (ref "C12") (pin "1") (pinfunction "1_1") (pintype "passive"))
      (node (ref "C13") (pin "1") (pinfunction "1_1") (pintype "passive"))
      (node (ref "C14") (pin "C") (pinfunction "-_C") (pintype "passive"))
      (node (ref "C15") (pin "C") (pinfunction "-_C") (pintype "passive"))
      (node (ref "C16") (pin "2") (pinfunction "2_2") (pintype "passive"))
      (node (ref "C17") (pin "C") (pinfunction "-_C") (pintype "passive"))
      (node (ref "C18") (pin "2") (pinfunction "2_2") (pintype "passive"))
      (node (ref "C19") (pin "2") (pinfunction "2_2") (pintype "passive"))
      (node (ref "C2") (pin "1") (pinfunction "1_1") (pintype "passive"))
      (node (ref "C20") (pin "2") (pinfunction "2_2") (pintype "passive"))
      (node (ref "C21") (pin "2") (pinfunction "2_2") (pintype "passive"))
      (node (ref "C3") (pin "2") (pinfunction "2_2") (pintype "passive"))
      (node (ref "C4") (pin "2") (pinfunction "2_2") (pintype "passive"))
      (node (ref "C5") (pin "1") (pinfunction "1_1") (pintype "passive"))
      (node (ref "C6") (pin "C") (pinfunction "-_C") (pintype "passive"))
      (node (ref "C7") (pin "2") (pinfunction "2_2") (pintype "passive"))
      (node (ref "C8") (pin "1") (pinfunction "1_1") (pintype "passive"))
      (node (ref "C9") (pin "1") (pinfunction "1_1") (pintype "passive"))
      (node (ref "JCK1") (pin "P1") (pinfunction "1_P1") (pintype "bidirectional"))
      (node (ref "JCK2") (pin "P1") (pinfunction "1_P1") (pintype "bidirectional"))
      (node (ref "JP1") (pin "6") (pinfunction "6_6") (pintype "passive"))
      (node (ref "JP10") (pin "6") (pinfunction "6_6") (pintype "passive"))
      (node (ref "JP11") (pin "1") (pinfunction "1_1") (pintype "passive"))
      (node (ref "JP13") (pin "1") (pinfunction "1_1") (pintype "passive"))
      (node (ref "JP14") (pin "1") (pinfunction "1_1") (pintype "passive"))
      (node (ref "JP19") (pin "2") (pinfunction "2_2") (pintype "passive"))
      (node (ref "JP2") (pin "1") (pinfunction "1_1") (pintype "passive"))
      (node (ref "JP2") (pin "10") (pinfunction "10_10") (pintype "passive"))
      (node (ref "JP2") (pin "12") (pinfunction "12_12") (pintype "passive"))
      (node (ref "JP2") (pin "3") (pinfunction "3_3") (pintype "passive"))
      (node (ref "JP20") (pin "2") (pinfunction "2_2") (pintype "passive"))
      (node (ref "LED1") (pin "K") (pinfunction "C_K") (pintype "passive"))
      (node (ref "MODUL1") (pin "1") (pinfunction "GND_1") (pintype "bidirectional"))
      (node (ref "MODUL1") (pin "12") (pinfunction "GND1_12") (pintype "bidirectional"))
      (node (ref "MODUL1") (pin "28") (pinfunction "GND4_28") (pintype "bidirectional"))
      (node (ref "MODUL1") (pin "29") (pinfunction "GND5_29") (pintype "bidirectional"))
      (node (ref "R10") (pin "2") (pinfunction "2_2") (pintype "passive"))
      (node (ref "R11") (pin "2") (pinfunction "2_2") (pintype "passive"))
      (node (ref "R13") (pin "1") (pinfunction "1_1") (pintype "passive"))
      (node (ref "R15") (pin "1") (pinfunction "1_1") (pintype "passive"))
      (node (ref "R16") (pin "2") (pinfunction "2_2") (pintype "passive"))
      (node (ref "R17") (pin "2") (pinfunction "2_2") (pintype "passive"))
      (node (ref "R19") (pin "1") (pinfunction "1_1") (pintype "passive"))
      (node (ref "R22") (pin "2") (pinfunction "2_2") (pintype "passive"))
      (node (ref "R23") (pin "1") (pinfunction "1_1") (pintype "passive"))
      (node (ref "R25") (pin "1") (pinfunction "1_1") (pintype "passive"))
      (node (ref "R9") (pin "2") (pinfunction "2_2") (pintype "passive"))
      (node (ref "TP8") (pin "1") (pinfunction "P$1_1") (pintype "bidirectional"))
      (node (ref "TP9") (pin "1") (pinfunction "P$1_1") (pintype "bidirectional"))
      (node (ref "U1") (pin "21") (pinfunction "GND_21") (pintype "bidirectional"))
      (node (ref "U1") (pin "3") (pinfunction "GND_3") (pintype "bidirectional"))
      (node (ref "U1") (pin "5") (pinfunction "AGND_5") (pintype "bidirectional"))
      (node (ref "U2") (pin "6") (pinfunction "GND_6") (pintype "bidirectional"))
      (node (ref "U2") (pin "CD2") (pinfunction "CD2_CD2") (pintype "bidirectional"))
      (node (ref "U2") (pin "GND1") (pinfunction "SHIELD1_GND1") (pintype "bidirectional"))
      (node (ref "U2") (pin "GND2") (pinfunction "SHIELD2_GND2") (pintype "bidirectional"))
      (node (ref "U3") (pin "10") (pinfunction "10_10") (pintype "passive"))
      (node (ref "U3") (pin "11") (pinfunction "11_11") (pintype "passive"))
      (node (ref "U3") (pin "12") (pinfunction "12_12") (pintype "passive"))
      (node (ref "U3") (pin "13") (pinfunction "13_13") (pintype "passive"))
      (node (ref "U3") (pin "15") (pinfunction "15_15") (pintype "passive"))
      (node (ref "U3") (pin "4") (pinfunction "4_4") (pintype "passive"))
      (node (ref "U3") (pin "5") (pinfunction "5_5") (pintype "passive"))
      (node (ref "U3") (pin "6") (pinfunction "6_6") (pintype "passive"))
      (node (ref "U3") (pin "7") (pinfunction "7_7") (pintype "passive"))
      (node (ref "U3") (pin "8") (pinfunction "8_8") (pintype "passive"))
      (node (ref "U3") (pin "9") (pinfunction "9_9") (pintype "passive"))
      (node (ref "U4") (pin "EP") (pinfunction "EP_EP") (pintype "bidirectional"))
      (node (ref "U4") (pin "P20") (pinfunction "AGND_P20") (pintype "bidirectional"))
      (node (ref "U5") (pin "2") (pinfunction "GND_2") (pintype "input"))
      (node (ref "X1") (pin "P4") (pinfunction "GND_P4") (pintype "bidirectional"))
      (node (ref "X2") (pin "GND") (pinfunction "GND_GND") (pintype "bidirectional"))
    )
    (net (code "56") (name "Net-(JP2-Pad5)") (class "Default")
      (node (ref "JP2") (pin "5") (pinfunction "5_5") (pintype "passive"))
      (node (ref "JP2") (pin "8") (pinfunction "8_8") (pintype "passive"))
      (node (ref "SJ1") (pin "2") (pinfunction "2_2") (pintype "passive"))
    )
    (net (code "57") (name "Net-(LED1-PadA)") (class "Default")
      (node (ref "LED1") (pin "A") (pinfunction "A_A") (pintype "passive"))
      (node (ref "R6") (pin "1") (pinfunction "1_1") (pintype "passive"))
    )
    (net (code "58") (name "Net-(LED2-C)") (class "Default")
      (node (ref "LED2") (pin "K") (pinfunction "C_K") (pintype "passive"))
      (node (ref "R9") (pin "1") (pinfunction "1_1") (pintype "passive"))
    )
    (net (code "59") (name "Net-(LED3-C)") (class "Default")
      (node (ref "LED3") (pin "K") (pinfunction "C_K") (pintype "passive"))
      (node (ref "U4") (pin "P15") (pinfunction "ILED_P15") (pintype "bidirectional"))
    )
    (net (code "60") (name "Net-(LED3-PadA)") (class "Default")
      (node (ref "LED3") (pin "A") (pinfunction "A_A") (pintype "passive"))
      (node (ref "R12") (pin "1") (pinfunction "1_1") (pintype "passive"))
    )
    (net (code "61") (name "Net-(LED4-PadC)") (class "Default")
      (node (ref "LED4") (pin "C") (pinfunction "C_C") (pintype "passive"))
      (node (ref "R11") (pin "1") (pinfunction "1_1") (pintype "passive"))
    )
    (net (code "62") (name "Net-(LED5-PadC)") (class "Default")
      (node (ref "LED5") (pin "C") (pinfunction "C_C") (pintype "passive"))
      (node (ref "R16") (pin "1") (pinfunction "1_1") (pintype "passive"))
    )
    (net (code "63") (name "Net-(LED6-C)") (class "Default")
      (node (ref "LED6") (pin "K") (pinfunction "C_K") (pintype "passive"))
      (node (ref "R17") (pin "1") (pinfunction "1_1") (pintype "passive"))
    )
    (net (code "64") (name "Net-(Q2-G)") (class "Default")
      (node (ref "C19") (pin "1") (pinfunction "1_1") (pintype "passive"))
      (node (ref "Q2") (pin "P1") (pinfunction "G_P1") (pintype "bidirectional"))
      (node (ref "R21") (pin "2") (pinfunction "2_2") (pintype "passive"))
      (node (ref "R22") (pin "1") (pinfunction "1_1") (pintype "passive"))
    )
    (net (code "65") (name "Net-(R5-Pad1)") (class "Default")
      (node (ref "R5") (pin "1") (pinfunction "1_1") (pintype "passive"))
      (node (ref "X2") (pin "D+") (pinfunction "D+_D+") (pintype "bidirectional"))
    )
    (net (code "66") (name "Net-(R5-Pad2)") (class "Default")
      (node (ref "R5") (pin "2") (pinfunction "2_2") (pintype "passive"))
      (node (ref "X2") (pin "D-") (pinfunction "D-_D-") (pintype "bidirectional"))
    )
    (net (code "67") (name "Net-(SG1-2)") (class "Default")
      (node (ref "R20") (pin "2") (pinfunction "2_2") (pintype "passive"))
      (node (ref "SG1") (pin "-") (pinfunction "2_-") (pintype "passive"))
    )
    (net (code "68") (name "Net-(U4-CBYP)") (class "Default")
      (node (ref "C7") (pin "1") (pinfunction "1_1") (pintype "passive"))
      (node (ref "U4") (pin "P19") (pinfunction "CBYP_P19") (pintype "bidirectional"))
    )
    (net (code "69") (name "Net-(U4-DIGIO1)") (class "Default")
      (node (ref "R24") (pin "2") (pinfunction "2_2") (pintype "passive"))
      (node (ref "U4") (pin "P5") (pinfunction "DIGIO1_P5") (pintype "bidirectional"))
    )
    (net (code "70") (name "Net-(U4-DIGIO2)") (class "Default")
      (node (ref "R25") (pin "2") (pinfunction "2_2") (pintype "passive"))
      (node (ref "U4") (pin "P3") (pinfunction "DIGIO2_P3") (pintype "bidirectional"))
    )
    (net (code "71") (name "Net-(U4-DIGIO3)") (class "Default")
      (node (ref "R26") (pin "2") (pinfunction "2_2") (pintype "passive"))
      (node (ref "U4") (pin "P2") (pinfunction "DIGIO3_P2") (pintype "bidirectional"))
    )
    (net (code "72") (name "Net-(U4-THR)") (class "Default")
      (node (ref "R10") (pin "1") (pinfunction "1_1") (pintype "passive"))
      (node (ref "U4") (pin "P18") (pinfunction "THR_P18") (pintype "bidirectional"))
    )
    (net (code "73") (name "Net-(U5-BP)") (class "Default")
      (node (ref "C16") (pin "1") (pinfunction "1_1") (pintype "passive"))
      (node (ref "U5") (pin "4") (pinfunction "BP_4") (pintype "input"))
    )
    (net (code "74") (name "VCC") (class "Default")
      (node (ref "C11") (pin "2") (pinfunction "2_2") (pintype "passive"))
      (node (ref "C12") (pin "2") (pinfunction "2_2") (pintype "passive"))
      (node (ref "C13") (pin "2") (pinfunction "2_2") (pintype "passive"))
      (node (ref "C17") (pin "A") (pinfunction "+_A") (pintype "passive"))
      (node (ref "C18") (pin "1") (pinfunction "1_1") (pintype "passive"))
      (node (ref "C20") (pin "1") (pinfunction "1_1") (pintype "passive"))
      (node (ref "C8") (pin "2") (pinfunction "2_2") (pintype "passive"))
      (node (ref "C9") (pin "2") (pinfunction "2_2") (pintype "passive"))
      (node (ref "JCK1") (pin "P3") (pinfunction "3_P3") (pintype "bidirectional"))
      (node (ref "JCK1") (pin "P5") (pinfunction "5_P5") (pintype "bidirectional"))
      (node (ref "JCK2") (pin "P3") (pinfunction "3_P3") (pintype "bidirectional"))
      (node (ref "JCK2") (pin "P5") (pinfunction "5_P5") (pintype "bidirectional"))
      (node (ref "JP10") (pin "2") (pinfunction "2_2") (pintype "passive"))
      (node (ref "JP11") (pin "2") (pinfunction "2_2") (pintype "passive"))
      (node (ref "JP13") (pin "4") (pinfunction "4_4") (pintype "passive"))
      (node (ref "JP19") (pin "1") (pinfunction "1_1") (pintype "passive"))
      (node (ref "JP20") (pin "1") (pinfunction "1_1") (pintype "passive"))
      (node (ref "Q2") (pin "P2") (pinfunction "S_P2") (pintype "bidirectional"))
      (node (ref "R1") (pin "2") (pinfunction "2_2") (pintype "passive"))
      (node (ref "R4") (pin "2") (pinfunction "2_2") (pintype "passive"))
      (node (ref "R7") (pin "2") (pinfunction "2_2") (pintype "passive"))
      (node (ref "R8") (pin "2") (pinfunction "2_2") (pintype "passive"))
      (node (ref "S2") (pin "3") (pinfunction "3_3") (pintype "passive"))
      (node (ref "S2") (pin "4") (pinfunction "4_4") (pintype "passive"))
      (node (ref "SG1") (pin "+") (pinfunction "1_+") (pintype "passive"))
      (node (ref "SJ1") (pin "1") (pinfunction "1_1") (pintype "passive"))
      (node (ref "U1") (pin "18") (pinfunction "AVCC_18") (pintype "bidirectional"))
      (node (ref "U1") (pin "4") (pinfunction "VCC_4") (pintype "bidirectional"))
      (node (ref "U1") (pin "6") (pinfunction "VCC_6") (pintype "bidirectional"))
      (node (ref "U2") (pin "4") (pinfunction "VCC_4") (pintype "bidirectional"))
      (node (ref "U5") (pin "5") (pinfunction "OUT_5") (pintype "passive"))
    )
    (net (code "75") (name "unconnected-(JP2-Pad2)") (class "Default")
      (node (ref "JP2") (pin "2") (pinfunction "2_2") (pintype "passive"))
    )
    (net (code "76") (name "unconnected-(MODUL1-AIO1-Pad35)") (class "Default")
      (node (ref "MODUL1") (pin "35") (pinfunction "AIO1_35") (pintype "bidirectional"))
    )
    (net (code "77") (name "unconnected-(MODUL1-AIO2-Pad30)") (class "Default")
      (node (ref "MODUL1") (pin "30") (pinfunction "AIO2_30") (pintype "bidirectional"))
    )
    (net (code "78") (name "unconnected-(MODUL1-GND2-Pad25)") (class "Default")
      (node (ref "MODUL1") (pin "25") (pinfunction "GND2_25") (pintype "bidirectional"))
    )
    (net (code "79") (name "unconnected-(MODUL1-GND3-Pad27)") (class "Default")
      (node (ref "MODUL1") (pin "27") (pinfunction "GND3_27") (pintype "bidirectional"))
    )
    (net (code "80") (name "unconnected-(MODUL1-NC-Pad26)") (class "Default")
      (node (ref "MODUL1") (pin "26") (pinfunction "NC_26") (pintype "bidirectional"))
    )
    (net (code "81") (name "unconnected-(MODUL1-PCMCLK-Pad7)") (class "Default")
      (node (ref "MODUL1") (pin "7") (pinfunction "PCMCLK_7") (pintype "bidirectional"))
    )
    (net (code "82") (name "unconnected-(MODUL1-PCMIN-Pad9)") (class "Default")
      (node (ref "MODUL1") (pin "9") (pinfunction "PCMIN_9") (pintype "bidirectional"))
    )
    (net (code "83") (name "unconnected-(MODUL1-PCMOUT-Pad10)") (class "Default")
      (node (ref "MODUL1") (pin "10") (pinfunction "PCMOUT_10") (pintype "bidirectional"))
    )
    (net (code "84") (name "unconnected-(MODUL1-PCMSYNC-Pad8)") (class "Default")
      (node (ref "MODUL1") (pin "8") (pinfunction "PCMSYNC_8") (pintype "bidirectional"))
    )
    (net (code "85") (name "unconnected-(MODUL1-PIO9-Pad32)") (class "Default")
      (node (ref "MODUL1") (pin "32") (pinfunction "PIO9_32") (pintype "bidirectional"))
    )
    (net (code "86") (name "unconnected-(MODUL1-PIO10-Pad33)") (class "Default")
      (node (ref "MODUL1") (pin "33") (pinfunction "PIO10_33") (pintype "bidirectional"))
    )
    (net (code "87") (name "unconnected-(MODUL1-PIO11-Pad34)") (class "Default")
      (node (ref "MODUL1") (pin "34") (pinfunction "PIO11_34") (pintype "bidirectional"))
    )
    (net (code "88") (name "unconnected-(MODUL1-USBD+-Pad17)") (class "Default")
      (node (ref "MODUL1") (pin "17") (pinfunction "USBD+_17") (pintype "bidirectional"))
    )
    (net (code "89") (name "unconnected-(MODUL1-USBD--Pad18)") (class "Default")
      (node (ref "MODUL1") (pin "18") (pinfunction "USBD-_18") (pintype "bidirectional"))
    )
    (net (code "90") (name "unconnected-(S3-O-Pad1)") (class "Default")
      (node (ref "S3") (pin "1") (pinfunction "O_1") (pintype "passive"))
    )
    (net (code "91") (name "unconnected-(U2-NC-Pad1)") (class "Default")
      (node (ref "U2") (pin "1") (pinfunction "NC_1") (pintype "bidirectional"))
    )
    (net (code "92") (name "unconnected-(U2-PadCD1)") (class "Default")
      (node (ref "U2") (pin "CD1") (pinfunction "CD1_CD1") (pintype "bidirectional"))
    )
    (net (code "93") (name "unconnected-(U2-RSV-Pad8)") (class "Default")
      (node (ref "U2") (pin "8") (pinfunction "RSV_8") (pintype "bidirectional"))
    )
    (net (code "94") (name "unconnected-(U4-SYS_EN-PadP16)") (class "Default")
      (node (ref "U4") (pin "P16") (pinfunction "SYS_EN_P16") (pintype "bidirectional"))
    )
  )
)
